# PowerDistribution.net
KiCad netlist of a schematic drawn in Altium Designer
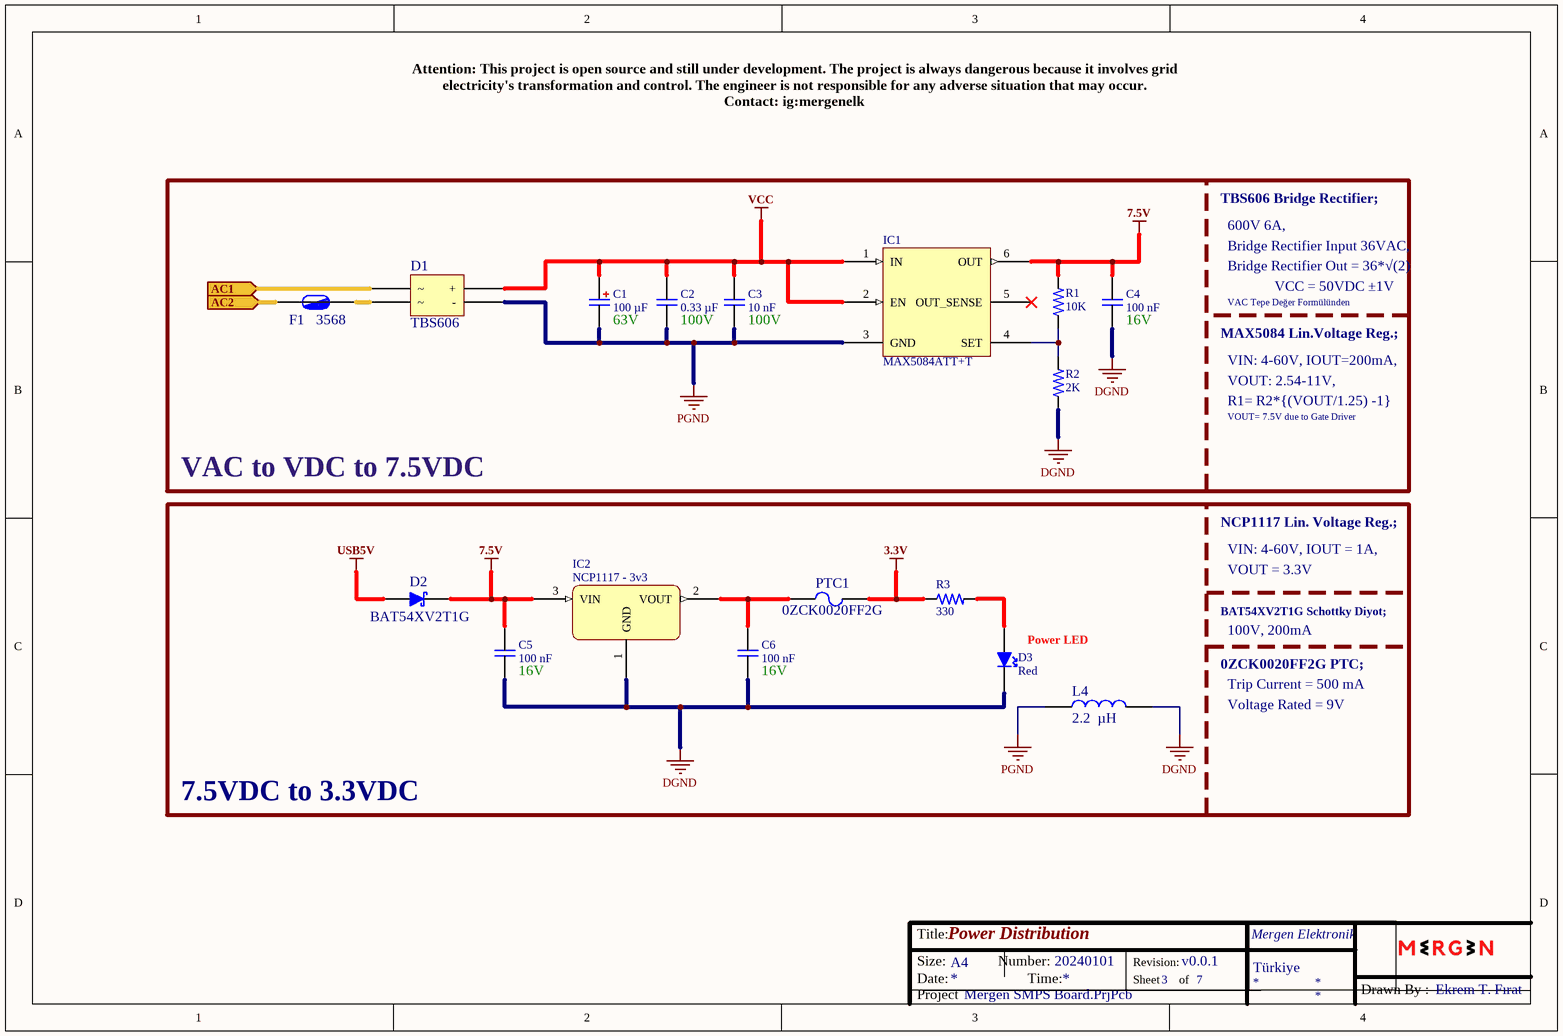
[diagram p0: PowerDistribution.SchDoc]

(export (version "E")
  (design (tool "Eeschema 10.0.6"))
  (components
    (comp (ref "C1")
      (value "100 µF")
      (footprint "MergenElektronik_Capacitors_AluminumElectrolytics_SMDs_10x10.5mm")
      (description "Mergen Elektronik - Capacitors - Aluminum Electrolytics - SMDs - UUX1J101MNL1GS")
      (fields
        (field (name "MANUFACTURER") "Nichicon")
        (field (name "TOLERANCE") "±20%")
        (field (name "VOLTAGE RATED") "63V")
      )
      (libsource (lib "MergenElektronik_Capacitors_AluminumElectrolytics_SMDs") (part "MergenElektronik_Capacitors_AluminumElectrolytics_SMDs_UUX1J101MNL1GS"))
    )
    (comp (ref "C2")
      (value "0.33 µF")
      (footprint "MergenElektronik_Capacitors_Ceramics_SMDs_1206_L")
      (description "Mergen Elektronik - Capacitors - Ceramics - SMDs - 1206 - 0.33 µF - 100V")
      (fields
        (field (name "MANUFACTURER") "TDK Corporation")
        (field (name "TOLERANCE") "±10%")
        (field (name "VOLTAGE RATED") "100V")
      )
      (libsource (lib "MergenElektronik_Capacitors_Ceramics_SMDs") (part "MergenElektronik_Capacitors_Ceramic_SMDs_0.33µF_100V"))
    )
    (comp (ref "C3")
      (value "10 nF")
      (footprint "MergenElektronik_Capacitors_Ceramics_SMDs_0603_L")
      (description "Mergen Elektronik - Capacitors - Ceramics - SMDs - 0603 - 10 nF - 100V")
      (fields
        (field (name "MANUFACTURER") "Murata Electronics")
        (field (name "TOLERANCE") "±10%")
        (field (name "VOLTAGE RATED") "100V")
      )
      (libsource (lib "MergenElektronik_Capacitors_Ceramics_SMDs") (part "MergenElektronik_Capacitors_Ceramic_SMDs_10nF_100V"))
    )
    (comp (ref "C4")
      (value "100 nF")
      (footprint "MergenElektronik_Capacitors_Ceramics_SMDs_0603_M")
      (description "Mergen Elektronik - Capacitors - Ceramics - SMDs - 0603 - 100 nF - 16V")
      (fields
        (field (name "MANUFACTURER") "Samsung Electro-Mechanics")
        (field (name "TOLERANCE") "±10%")
        (field (name "VOLTAGE RATED") "16V")
      )
      (libsource (lib "MergenElektronik_Capacitors_Ceramics_SMDs") (part "MergenElektronik_Capacitors_Ceramic_SMDs_100nF_16V"))
    )
    (comp (ref "C5")
      (value "100 nF")
      (footprint "MergenElektronik_Capacitors_Ceramics_SMDs_0603_M")
      (description "Mergen Elektronik - Capacitors - Ceramics - SMDs - 0603 - 100 nF - 16V")
      (fields
        (field (name "MANUFACTURER") "Samsung Electro-Mechanics")
        (field (name "TOLERANCE") "±10%")
        (field (name "VOLTAGE RATED") "16V")
      )
      (libsource (lib "MergenElektronik_Capacitors_Ceramics_SMDs") (part "MergenElektronik_Capacitors_Ceramic_SMDs_100nF_16V"))
    )
    (comp (ref "C6")
      (value "100 nF")
      (footprint "MergenElektronik_Capacitors_Ceramics_SMDs_0603_M")
      (description "Mergen Elektronik - Capacitors - Ceramics - SMDs - 0603 - 100 nF - 16V")
      (fields
        (field (name "MANUFACTURER") "Samsung Electro-Mechanics")
        (field (name "TOLERANCE") "±10%")
        (field (name "VOLTAGE RATED") "16V")
      )
      (libsource (lib "MergenElektronik_Capacitors_Ceramics_SMDs") (part "MergenElektronik_Capacitors_Ceramic_SMDs_100nF_16V"))
    )
    (comp (ref "D1")
      (value "TBS606")
      (footprint "MergenElektronik_Diodes_BridgeRectifiers_TBS606")
      (description "Mergen Elektronik - Diodes - Bridge Rectifiers - TBS606")
      (fields (field (name "MANUFACTURER") "Taiwan Semiconductor Corporation"))
      (libsource (lib "MergenElektronik_Diodes_BridgeRectifiers") (part "MergenElektronik_Diodes_BridgeRectifiers_TBS606"))
    )
    (comp (ref "D2")
      (value "BAT54XV2T1G")
      (footprint "MergenElektronik_Diodes_SchottkyDiodes_SOD-523")
      (description "Mergen Elektronik - Diodes - Schottky Diodes - BAT54XV2T1G")
      (fields (field (name "MANUFACTURER") "onsemi"))
      (libsource (lib "MergenElektronik_Diodes_SchottkyDiodes") (part "MergenElektronik_Diodes_SchottkyDiodes_BAT54XV2T1G"))
    )
    (comp (ref "D3")
      (value "Red")
      (footprint "MergenElektronik_Leds_SMDs_0603_S_NS")
      (description "Mergen Elektronik - Leds - SMDs - Red - 0603")
      (fields (field (name "MANUFACTURER") "Würth Elektronik"))
      (libsource (lib "MergenElektronik_Leds_SMDs") (part "MergenElektronik_LEDs_SMDs_Red_0603"))
    )
    (comp (ref "F1")
      (value "3568")
      (footprint "MergenElektronik_FuseHolders_BladeType_3568")
      (description "Mergen Elektronik - Fuse Holder - Blade Type - 3568")
      (fields (field (name "MANUFACTURER") "Keystone Electronics"))
      (libsource (lib "MergenElektronik_FuseHolders_BladeType") (part "MergenElektronik_FuseHolders_BladeType_3568"))
    )
    (comp (ref "IC1")
      (value "MAX5084ATT+T")
      (footprint "MergenElektronik_Regulators_Linears_6-TDFN")
      (description "Mergen Elektronik - Regulators - Linears - MAX5084ATT+T")
      (fields (field (name "MANUFACTURER") "Analog Devices Inc./Maxim Integrated"))
      (libsource (lib "MergenElektronik_Regulators_Linears") (part "MergenElektronik_Regulators_Linears_MAX5084ATT+T"))
    )
    (comp (ref "IC2")
      (value "NCP1117 - 3v3")
      (footprint "MergenElektronik_Regulators_Linears_SOT223")
      (description "Mergen Elektronik - Regulators - Linears - NCP1117ST33T3G")
      (fields (field (name "MANUFACTURER") "onsemi"))
      (libsource (lib "MergenElektronik_Regulators_Linears") (part "MergenElektronik_Regulators_Linears_NCP1117ST33T3G"))
    )
    (comp (ref "L4")
      (value "2.2  µH")
      (footprint "MergenElektronik_Inductors_PowerInductors_SMDs_1008_S_NS")
      (description "Mergen Elektronik - Inductors - Power Inductors - SMDs - 1008 - 2.2 µh - 2A")
      (fields (field (name "MANUFACTURER") "Samsung Electro-Mechanics"))
      (libsource (lib "MergenElektronik_Inductors_PowerInductors_SMDs") (part "MergenElektronik_Inductors_PowerInductors_SMDs_1008_2.2µH-2A"))
    )
    (comp (ref "PTC1")
      (value "0ZCK0020FF2G")
      (footprint "MergenElektronik_CircuitProtections_PTCs_0603_M")
      (description "Mergen Elektronik - Circuit Protections - PTCs - 0ZCK0020FF2G")
      (fields (field (name "MANUFACTURER") "Bel Fuse Inc."))
      (libsource (lib "MergenElektronik_CircuitProtections_PTCs") (part "MergenElektronik_CircuitProtections_PTCs_0ZCK0020FF2G"))
    )
    (comp (ref "R1")
      (value "10K")
      (footprint "MergenElektronik_Resistors_ChipResistors_0603_S_NS")
      (description "Mergen Elektronik - Resistors - Chip Resistors - 0603 - 10K")
      (fields (field (name "MANUFACTURER") "Stackpole Electronics Inc") (field (name "POWER") "1/10W"))
      (libsource (lib "MergenElektronik_Resistors_ChipResistors") (part "MergenElektronik_Resistors_ChipResistors_0603_10K"))
    )
    (comp (ref "R2")
      (value "2K")
      (footprint "MergenElektronik_Resistors_ChipResistors_0603_S_NS")
      (description "Mergen Elektronik - Resistors - Chip Resistors - 0603 - 2K")
      (fields (field (name "MANUFACTURER") "Panasonic Electronic Components") (field (name "POWER") "1/10W"))
      (libsource (lib "MergenElektronik_Resistors_ChipResistors") (part "MergenElektronik_Resistors_ChipResistors_0603_2K"))
    )
    (comp (ref "R3")
      (value "330")
      (footprint "MergenElektronik_Resistors_ChipResistors_0603_S_NS")
      (description "Mergen Elektronik - Resistors - Chip Resistors - 0603 - 330R")
      (fields (field (name "MANUFACTURER") "Stackpole Electronics Inc") (field (name "POWER") "1/10W"))
      (libsource (lib "MergenElektronik_Resistors_ChipResistors") (part "MergenElektronik_Resistors_ChipResistors_0603_330R"))
    )
  )
  (nets
    (net (code "1") (name "/AC1") (class "Default")
      (node (ref "D1") (pin "3") (pinfunction "~_3") (pintype "power_in"))
    )
    (net (code "2") (name "/AC2") (class "Default")
      (node (ref "F1") (pin "1") (pinfunction "1_1") (pintype "passive"))
    )
    (net (code "3") (name "3.3V") (class "Default")
      (node (ref "PTC1") (pin "2") (pinfunction "2_2") (pintype "passive"))
      (node (ref "R3") (pin "1") (pinfunction "1_1") (pintype "passive"))
    )
    (net (code "4") (name "7.5V") (class "Default")
      (node (ref "C4") (pin "1") (pinfunction "1_1") (pintype "passive"))
      (node (ref "C5") (pin "1") (pinfunction "1_1") (pintype "passive"))
      (node (ref "D2") (pin "2") (pinfunction "KATOT_2") (pintype "passive"))
      (node (ref "IC1") (pin "6") (pinfunction "OUT_6") (pintype "output"))
      (node (ref "IC2") (pin "3") (pinfunction "VIN_3") (pintype "input"))
      (node (ref "R1") (pin "2") (pinfunction "2_2") (pintype "passive"))
    )
    (net (code "5") (name "DGND") (class "Default")
      (node (ref "C4") (pin "2") (pinfunction "2_2") (pintype "passive"))
      (node (ref "C5") (pin "2") (pinfunction "2_2") (pintype "passive"))
      (node (ref "C6") (pin "2") (pinfunction "2_2") (pintype "passive"))
      (node (ref "D3") (pin "2") (pinfunction "KATOT_2") (pintype "passive"))
      (node (ref "IC2") (pin "1") (pinfunction "GND_1") (pintype "power_in"))
      (node (ref "L4") (pin "2") (pinfunction "2_2") (pintype "passive"))
      (node (ref "R2") (pin "1") (pinfunction "1_1") (pintype "passive"))
    )
    (net (code "6") (name "Net-(D1-~-Pad4)") (class "Default")
      (node (ref "D1") (pin "4") (pinfunction "~_4") (pintype "power_in"))
      (node (ref "F1") (pin "2") (pinfunction "2_2") (pintype "passive"))
    )
    (net (code "7") (name "Net-(D3-ANOT)") (class "Default")
      (node (ref "D3") (pin "1") (pinfunction "ANOT_1") (pintype "passive"))
      (node (ref "R3") (pin "2") (pinfunction "2_2") (pintype "passive"))
    )
    (net (code "8") (name "Net-(IC1-SET)") (class "Default")
      (node (ref "IC1") (pin "4") (pinfunction "SET_4") (pintype "passive"))
      (node (ref "R1") (pin "1") (pinfunction "1_1") (pintype "passive"))
      (node (ref "R2") (pin "2") (pinfunction "2_2") (pintype "passive"))
    )
    (net (code "9") (name "Net-(IC2-VOUT)") (class "Default")
      (node (ref "C6") (pin "1") (pinfunction "1_1") (pintype "passive"))
      (node (ref "IC2") (pin "2") (pinfunction "VOUT_2") (pintype "output"))
      (node (ref "PTC1") (pin "1") (pinfunction "1_1") (pintype "passive"))
    )
    (net (code "10") (name "PGND") (class "Default")
      (node (ref "C1") (pin "1") (pinfunction "1_1") (pintype "passive"))
      (node (ref "C2") (pin "2") (pinfunction "2_2") (pintype "passive"))
      (node (ref "C3") (pin "2") (pinfunction "2_2") (pintype "passive"))
      (node (ref "D1") (pin "2") (pinfunction "-_2") (pintype "power_in"))
      (node (ref "IC1") (pin "3") (pinfunction "GND_3") (pintype "power_in"))
      (node (ref "L4") (pin "1") (pinfunction "1_1") (pintype "passive"))
    )
    (net (code "11") (name "USB5V") (class "Default")
      (node (ref "D2") (pin "1") (pinfunction "ANOT_1") (pintype "passive"))
    )
    (net (code "12") (name "VCC") (class "Default")
      (node (ref "C1") (pin "2") (pinfunction "2_2") (pintype "passive"))
      (node (ref "C2") (pin "1") (pinfunction "1_1") (pintype "passive"))
      (node (ref "C3") (pin "1") (pinfunction "1_1") (pintype "passive"))
      (node (ref "D1") (pin "1") (pinfunction "+_1") (pintype "power_in"))
      (node (ref "IC1") (pin "1") (pinfunction "IN_1") (pintype "input"))
      (node (ref "IC1") (pin "2") (pinfunction "EN_2") (pintype "input"))
    )
    (net (code "13") (name "unconnected-(IC1-OUT_SENSE-Pad5)") (class "Default")
      (node (ref "IC1") (pin "5") (pinfunction "OUT_SENSE_5") (pintype "passive+no_connect"))
    )
  )
)
